# charlie_array_v1.net
KiCad netlist of a schematic drawn in EAGLE
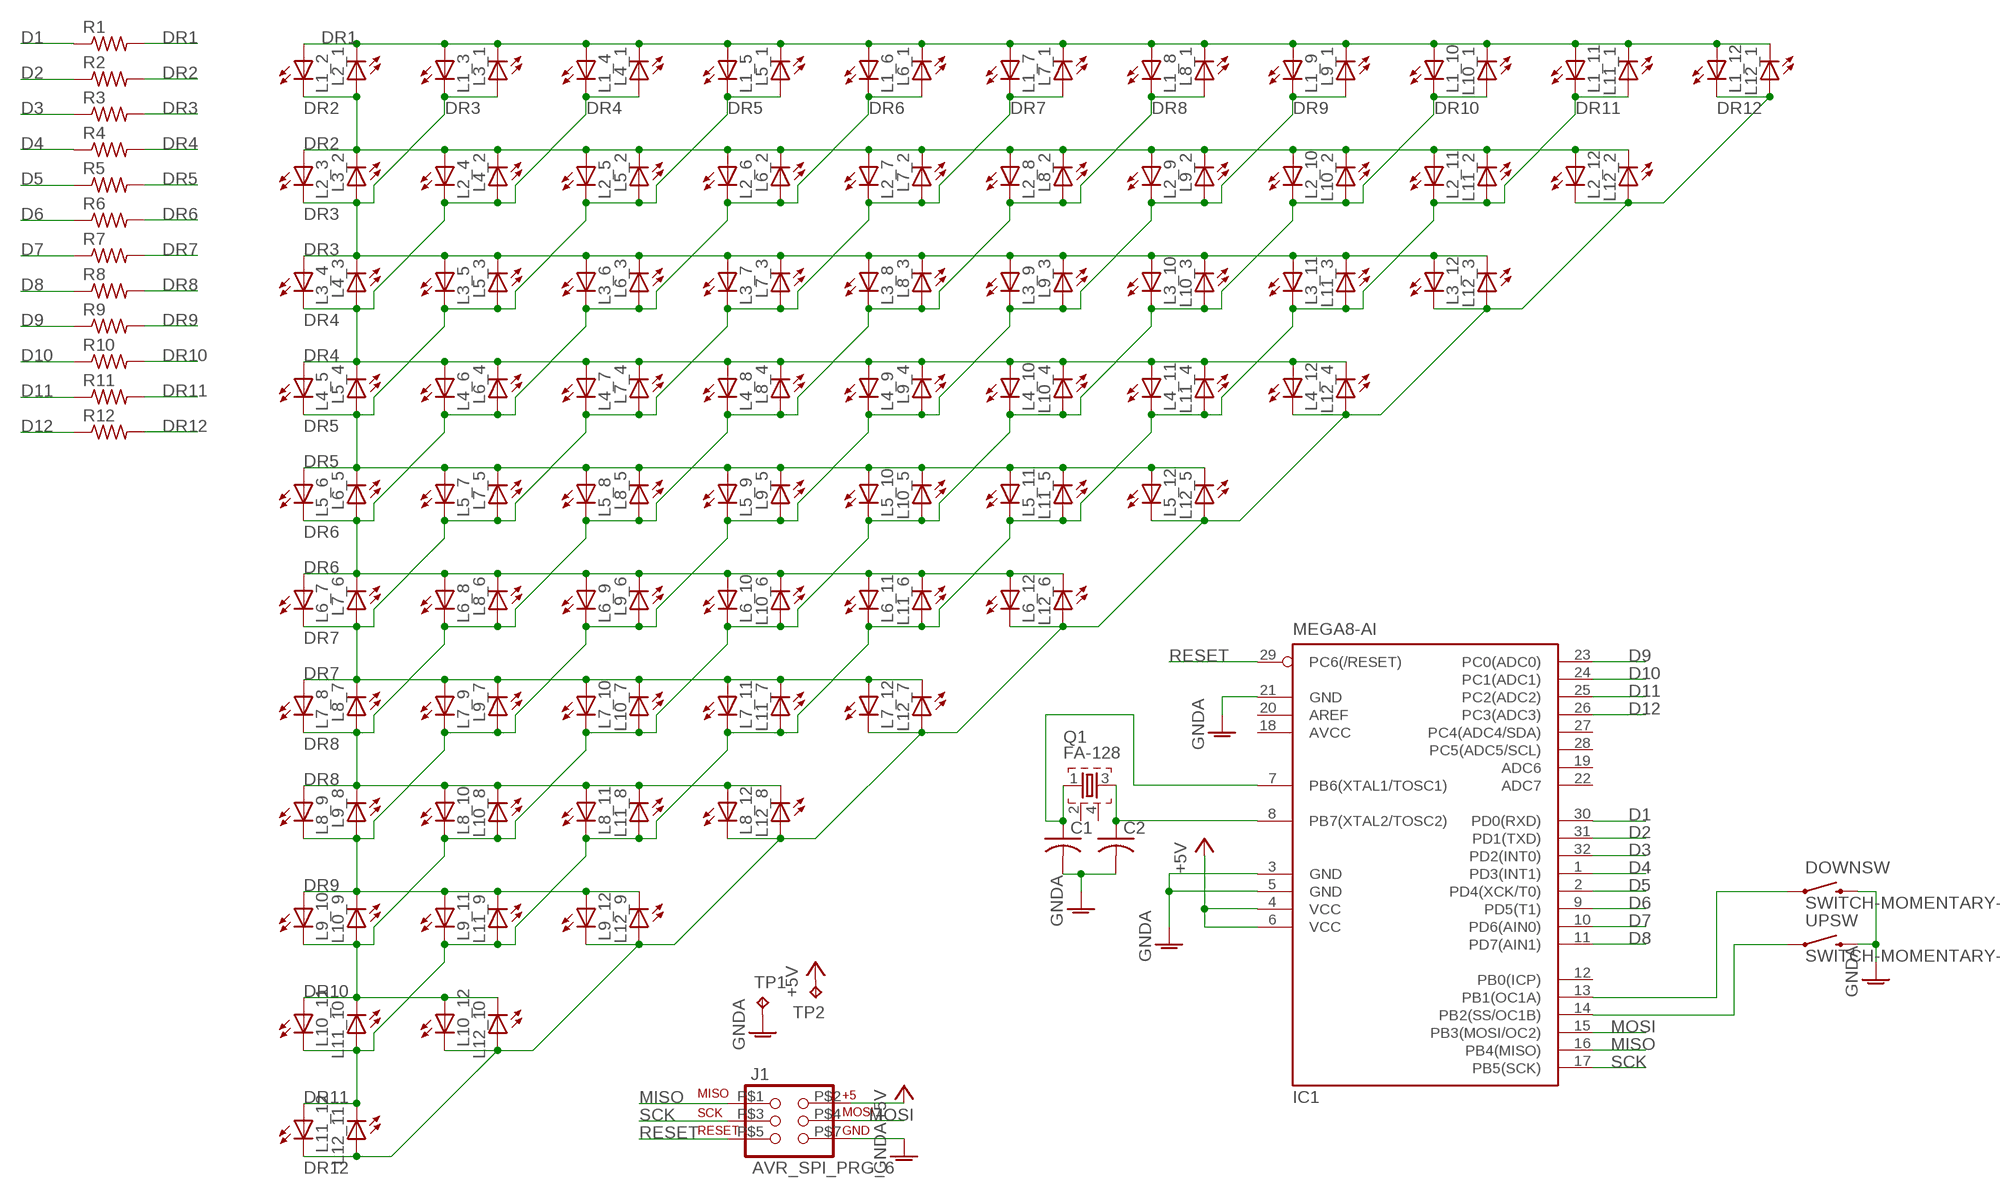
[diagram p0: schematic, sheet 1]

(export (version "E")
  (design (tool "Eeschema 10.0.6"))
  (components
    (comp (ref "C1")
      (value "C-USC0603")
      (footprint "eagle-import:C0603")
      (libsource (lib "eagle-import") (part "C-USC0603"))
    )
    (comp (ref "C2")
      (value "C-USC0603")
      (footprint "eagle-import:C0603")
      (libsource (lib "eagle-import") (part "C-USC0603"))
    )
    (comp (ref "DOWNSW")
      (value "SWITCH-MOMENTARY-2")
      (footprint "eagle-import:TACTILE_SWITCH_TALL")
      (libsource (lib "eagle-import") (part "SWITCH-MOMENTARY-2"))
    )
    (comp (ref "IC1")
      (value "MEGA8-AI")
      (footprint "eagle-import:TQFP32-08")
      (fields (field (name "MPN") "ATMEGA8-16AU"))
      (libsource (lib "eagle-import") (part "MEGA8-AI"))
    )
    (comp (ref "J1")
      (value "AVR_SPI_PRG_6")
      (footprint "eagle-import:2X3_ICSP_SMD")
      (libsource (lib "eagle-import") (part "AVR_SPI_PRG_6"))
    )
    (comp (ref "L1_2")
      (value "LEDCHIPLED_0603")
      (footprint "eagle-import:CHIPLED_0603")
      (libsource (lib "eagle-import") (part "LEDCHIPLED_0603"))
    )
    (comp (ref "L1_3")
      (value "LEDCHIPLED_0603")
      (footprint "eagle-import:CHIPLED_0603")
      (libsource (lib "eagle-import") (part "LEDCHIPLED_0603"))
    )
    (comp (ref "L1_4")
      (value "LEDCHIPLED_0603")
      (footprint "eagle-import:CHIPLED_0603")
      (libsource (lib "eagle-import") (part "LEDCHIPLED_0603"))
    )
    (comp (ref "L1_5")
      (value "LEDCHIPLED_0603")
      (footprint "eagle-import:CHIPLED_0603")
      (libsource (lib "eagle-import") (part "LEDCHIPLED_0603"))
    )
    (comp (ref "L1_6")
      (value "LEDCHIPLED_0603")
      (footprint "eagle-import:CHIPLED_0603")
      (libsource (lib "eagle-import") (part "LEDCHIPLED_0603"))
    )
    (comp (ref "L1_7")
      (value "LEDCHIPLED_0603")
      (footprint "eagle-import:CHIPLED_0603")
      (libsource (lib "eagle-import") (part "LEDCHIPLED_0603"))
    )
    (comp (ref "L1_8")
      (value "LEDCHIPLED_0603")
      (footprint "eagle-import:CHIPLED_0603")
      (libsource (lib "eagle-import") (part "LEDCHIPLED_0603"))
    )
    (comp (ref "L1_9")
      (value "LEDCHIPLED_0603")
      (footprint "eagle-import:CHIPLED_0603")
      (libsource (lib "eagle-import") (part "LEDCHIPLED_0603"))
    )
    (comp (ref "L1_10")
      (value "LEDCHIPLED_0603")
      (footprint "eagle-import:CHIPLED_0603")
      (libsource (lib "eagle-import") (part "LEDCHIPLED_0603"))
    )
    (comp (ref "L1_11")
      (value "LEDCHIPLED_0603")
      (footprint "eagle-import:CHIPLED_0603")
      (libsource (lib "eagle-import") (part "LEDCHIPLED_0603"))
    )
    (comp (ref "L1_12")
      (value "LEDCHIPLED_0603")
      (footprint "eagle-import:CHIPLED_0603")
      (libsource (lib "eagle-import") (part "LEDCHIPLED_0603"))
    )
    (comp (ref "L2_1")
      (value "LEDCHIPLED_0603")
      (footprint "eagle-import:CHIPLED_0603")
      (libsource (lib "eagle-import") (part "LEDCHIPLED_0603"))
    )
    (comp (ref "L2_3")
      (value "LEDCHIPLED_0603")
      (footprint "eagle-import:CHIPLED_0603")
      (libsource (lib "eagle-import") (part "LEDCHIPLED_0603"))
    )
    (comp (ref "L2_4")
      (value "LEDCHIPLED_0603")
      (footprint "eagle-import:CHIPLED_0603")
      (libsource (lib "eagle-import") (part "LEDCHIPLED_0603"))
    )
    (comp (ref "L2_5")
      (value "LEDCHIPLED_0603")
      (footprint "eagle-import:CHIPLED_0603")
      (libsource (lib "eagle-import") (part "LEDCHIPLED_0603"))
    )
    (comp (ref "L2_6")
      (value "LEDCHIPLED_0603")
      (footprint "eagle-import:CHIPLED_0603")
      (libsource (lib "eagle-import") (part "LEDCHIPLED_0603"))
    )
    (comp (ref "L2_7")
      (value "LEDCHIPLED_0603")
      (footprint "eagle-import:CHIPLED_0603")
      (libsource (lib "eagle-import") (part "LEDCHIPLED_0603"))
    )
    (comp (ref "L2_8")
      (value "LEDCHIPLED_0603")
      (footprint "eagle-import:CHIPLED_0603")
      (libsource (lib "eagle-import") (part "LEDCHIPLED_0603"))
    )
    (comp (ref "L2_9")
      (value "LEDCHIPLED_0603")
      (footprint "eagle-import:CHIPLED_0603")
      (libsource (lib "eagle-import") (part "LEDCHIPLED_0603"))
    )
    (comp (ref "L2_10")
      (value "LEDCHIPLED_0603")
      (footprint "eagle-import:CHIPLED_0603")
      (libsource (lib "eagle-import") (part "LEDCHIPLED_0603"))
    )
    (comp (ref "L2_11")
      (value "LEDCHIPLED_0603")
      (footprint "eagle-import:CHIPLED_0603")
      (libsource (lib "eagle-import") (part "LEDCHIPLED_0603"))
    )
    (comp (ref "L2_12")
      (value "LEDCHIPLED_0603")
      (footprint "eagle-import:CHIPLED_0603")
      (libsource (lib "eagle-import") (part "LEDCHIPLED_0603"))
    )
    (comp (ref "L3_1")
      (value "LEDCHIPLED_0603")
      (footprint "eagle-import:CHIPLED_0603")
      (libsource (lib "eagle-import") (part "LEDCHIPLED_0603"))
    )
    (comp (ref "L3_2")
      (value "LEDCHIPLED_0603")
      (footprint "eagle-import:CHIPLED_0603")
      (libsource (lib "eagle-import") (part "LEDCHIPLED_0603"))
    )
    (comp (ref "L3_4")
      (value "LEDCHIPLED_0603")
      (footprint "eagle-import:CHIPLED_0603")
      (libsource (lib "eagle-import") (part "LEDCHIPLED_0603"))
    )
    (comp (ref "L3_5")
      (value "LEDCHIPLED_0603")
      (footprint "eagle-import:CHIPLED_0603")
      (libsource (lib "eagle-import") (part "LEDCHIPLED_0603"))
    )
    (comp (ref "L3_6")
      (value "LEDCHIPLED_0603")
      (footprint "eagle-import:CHIPLED_0603")
      (libsource (lib "eagle-import") (part "LEDCHIPLED_0603"))
    )
    (comp (ref "L3_7")
      (value "LEDCHIPLED_0603")
      (footprint "eagle-import:CHIPLED_0603")
      (libsource (lib "eagle-import") (part "LEDCHIPLED_0603"))
    )
    (comp (ref "L3_8")
      (value "LEDCHIPLED_0603")
      (footprint "eagle-import:CHIPLED_0603")
      (libsource (lib "eagle-import") (part "LEDCHIPLED_0603"))
    )
    (comp (ref "L3_9")
      (value "LEDCHIPLED_0603")
      (footprint "eagle-import:CHIPLED_0603")
      (libsource (lib "eagle-import") (part "LEDCHIPLED_0603"))
    )
    (comp (ref "L3_10")
      (value "LEDCHIPLED_0603")
      (footprint "eagle-import:CHIPLED_0603")
      (libsource (lib "eagle-import") (part "LEDCHIPLED_0603"))
    )
    (comp (ref "L3_11")
      (value "LEDCHIPLED_0603")
      (footprint "eagle-import:CHIPLED_0603")
      (libsource (lib "eagle-import") (part "LEDCHIPLED_0603"))
    )
    (comp (ref "L3_12")
      (value "LEDCHIPLED_0603")
      (footprint "eagle-import:CHIPLED_0603")
      (libsource (lib "eagle-import") (part "LEDCHIPLED_0603"))
    )
    (comp (ref "L4_1")
      (value "LEDCHIPLED_0603")
      (footprint "eagle-import:CHIPLED_0603")
      (libsource (lib "eagle-import") (part "LEDCHIPLED_0603"))
    )
    (comp (ref "L4_2")
      (value "LEDCHIPLED_0603")
      (footprint "eagle-import:CHIPLED_0603")
      (libsource (lib "eagle-import") (part "LEDCHIPLED_0603"))
    )
    (comp (ref "L4_3")
      (value "LEDCHIPLED_0603")
      (footprint "eagle-import:CHIPLED_0603")
      (libsource (lib "eagle-import") (part "LEDCHIPLED_0603"))
    )
    (comp (ref "L4_5")
      (value "LEDCHIPLED_0603")
      (footprint "eagle-import:CHIPLED_0603")
      (libsource (lib "eagle-import") (part "LEDCHIPLED_0603"))
    )
    (comp (ref "L4_6")
      (value "LEDCHIPLED_0603")
      (footprint "eagle-import:CHIPLED_0603")
      (libsource (lib "eagle-import") (part "LEDCHIPLED_0603"))
    )
    (comp (ref "L4_7")
      (value "LEDCHIPLED_0603")
      (footprint "eagle-import:CHIPLED_0603")
      (libsource (lib "eagle-import") (part "LEDCHIPLED_0603"))
    )
    (comp (ref "L4_8")
      (value "LEDCHIPLED_0603")
      (footprint "eagle-import:CHIPLED_0603")
      (libsource (lib "eagle-import") (part "LEDCHIPLED_0603"))
    )
    (comp (ref "L4_9")
      (value "LEDCHIPLED_0603")
      (footprint "eagle-import:CHIPLED_0603")
      (libsource (lib "eagle-import") (part "LEDCHIPLED_0603"))
    )
    (comp (ref "L4_10")
      (value "LEDCHIPLED_0603")
      (footprint "eagle-import:CHIPLED_0603")
      (libsource (lib "eagle-import") (part "LEDCHIPLED_0603"))
    )
    (comp (ref "L4_11")
      (value "LEDCHIPLED_0603")
      (footprint "eagle-import:CHIPLED_0603")
      (libsource (lib "eagle-import") (part "LEDCHIPLED_0603"))
    )
    (comp (ref "L4_12")
      (value "LEDCHIPLED_0603")
      (footprint "eagle-import:CHIPLED_0603")
      (libsource (lib "eagle-import") (part "LEDCHIPLED_0603"))
    )
    (comp (ref "L5_1")
      (value "LEDCHIPLED_0603")
      (footprint "eagle-import:CHIPLED_0603")
      (libsource (lib "eagle-import") (part "LEDCHIPLED_0603"))
    )
    (comp (ref "L5_2")
      (value "LEDCHIPLED_0603")
      (footprint "eagle-import:CHIPLED_0603")
      (libsource (lib "eagle-import") (part "LEDCHIPLED_0603"))
    )
    (comp (ref "L5_3")
      (value "LEDCHIPLED_0603")
      (footprint "eagle-import:CHIPLED_0603")
      (libsource (lib "eagle-import") (part "LEDCHIPLED_0603"))
    )
    (comp (ref "L5_4")
      (value "LEDCHIPLED_0603")
      (footprint "eagle-import:CHIPLED_0603")
      (libsource (lib "eagle-import") (part "LEDCHIPLED_0603"))
    )
    (comp (ref "L5_6")
      (value "LEDCHIPLED_0603")
      (footprint "eagle-import:CHIPLED_0603")
      (libsource (lib "eagle-import") (part "LEDCHIPLED_0603"))
    )
    (comp (ref "L5_7")
      (value "LEDCHIPLED_0603")
      (footprint "eagle-import:CHIPLED_0603")
      (libsource (lib "eagle-import") (part "LEDCHIPLED_0603"))
    )
    (comp (ref "L5_8")
      (value "LEDCHIPLED_0603")
      (footprint "eagle-import:CHIPLED_0603")
      (libsource (lib "eagle-import") (part "LEDCHIPLED_0603"))
    )
    (comp (ref "L5_9")
      (value "LEDCHIPLED_0603")
      (footprint "eagle-import:CHIPLED_0603")
      (libsource (lib "eagle-import") (part "LEDCHIPLED_0603"))
    )
    (comp (ref "L5_10")
      (value "LEDCHIPLED_0603")
      (footprint "eagle-import:CHIPLED_0603")
      (libsource (lib "eagle-import") (part "LEDCHIPLED_0603"))
    )
    (comp (ref "L5_11")
      (value "LEDCHIPLED_0603")
      (footprint "eagle-import:CHIPLED_0603")
      (libsource (lib "eagle-import") (part "LEDCHIPLED_0603"))
    )
    (comp (ref "L5_12")
      (value "LEDCHIPLED_0603")
      (footprint "eagle-import:CHIPLED_0603")
      (libsource (lib "eagle-import") (part "LEDCHIPLED_0603"))
    )
    (comp (ref "L6_1")
      (value "LEDCHIPLED_0603")
      (footprint "eagle-import:CHIPLED_0603")
      (libsource (lib "eagle-import") (part "LEDCHIPLED_0603"))
    )
    (comp (ref "L6_2")
      (value "LEDCHIPLED_0603")
      (footprint "eagle-import:CHIPLED_0603")
      (libsource (lib "eagle-import") (part "LEDCHIPLED_0603"))
    )
    (comp (ref "L6_3")
      (value "LEDCHIPLED_0603")
      (footprint "eagle-import:CHIPLED_0603")
      (libsource (lib "eagle-import") (part "LEDCHIPLED_0603"))
    )
    (comp (ref "L6_4")
      (value "LEDCHIPLED_0603")
      (footprint "eagle-import:CHIPLED_0603")
      (libsource (lib "eagle-import") (part "LEDCHIPLED_0603"))
    )
    (comp (ref "L6_5")
      (value "LEDCHIPLED_0603")
      (footprint "eagle-import:CHIPLED_0603")
      (libsource (lib "eagle-import") (part "LEDCHIPLED_0603"))
    )
    (comp (ref "L6_7")
      (value "LEDCHIPLED_0603")
      (footprint "eagle-import:CHIPLED_0603")
      (libsource (lib "eagle-import") (part "LEDCHIPLED_0603"))
    )
    (comp (ref "L6_8")
      (value "LEDCHIPLED_0603")
      (footprint "eagle-import:CHIPLED_0603")
      (libsource (lib "eagle-import") (part "LEDCHIPLED_0603"))
    )
    (comp (ref "L6_9")
      (value "LEDCHIPLED_0603")
      (footprint "eagle-import:CHIPLED_0603")
      (libsource (lib "eagle-import") (part "LEDCHIPLED_0603"))
    )
    (comp (ref "L6_10")
      (value "LEDCHIPLED_0603")
      (footprint "eagle-import:CHIPLED_0603")
      (libsource (lib "eagle-import") (part "LEDCHIPLED_0603"))
    )
    (comp (ref "L6_11")
      (value "LEDCHIPLED_0603")
      (footprint "eagle-import:CHIPLED_0603")
      (libsource (lib "eagle-import") (part "LEDCHIPLED_0603"))
    )
    (comp (ref "L6_12")
      (value "LEDCHIPLED_0603")
      (footprint "eagle-import:CHIPLED_0603")
      (libsource (lib "eagle-import") (part "LEDCHIPLED_0603"))
    )
    (comp (ref "L7_1")
      (value "LEDCHIPLED_0603")
      (footprint "eagle-import:CHIPLED_0603")
      (libsource (lib "eagle-import") (part "LEDCHIPLED_0603"))
    )
    (comp (ref "L7_2")
      (value "LEDCHIPLED_0603")
      (footprint "eagle-import:CHIPLED_0603")
      (libsource (lib "eagle-import") (part "LEDCHIPLED_0603"))
    )
    (comp (ref "L7_3")
      (value "LEDCHIPLED_0603")
      (footprint "eagle-import:CHIPLED_0603")
      (libsource (lib "eagle-import") (part "LEDCHIPLED_0603"))
    )
    (comp (ref "L7_4")
      (value "LEDCHIPLED_0603")
      (footprint "eagle-import:CHIPLED_0603")
      (libsource (lib "eagle-import") (part "LEDCHIPLED_0603"))
    )
    (comp (ref "L7_5")
      (value "LEDCHIPLED_0603")
      (footprint "eagle-import:CHIPLED_0603")
      (libsource (lib "eagle-import") (part "LEDCHIPLED_0603"))
    )
    (comp (ref "L7_6")
      (value "LEDCHIPLED_0603")
      (footprint "eagle-import:CHIPLED_0603")
      (libsource (lib "eagle-import") (part "LEDCHIPLED_0603"))
    )
    (comp (ref "L7_8")
      (value "LEDCHIPLED_0603")
      (footprint "eagle-import:CHIPLED_0603")
      (libsource (lib "eagle-import") (part "LEDCHIPLED_0603"))
    )
    (comp (ref "L7_9")
      (value "LEDCHIPLED_0603")
      (footprint "eagle-import:CHIPLED_0603")
      (libsource (lib "eagle-import") (part "LEDCHIPLED_0603"))
    )
    (comp (ref "L7_10")
      (value "LEDCHIPLED_0603")
      (footprint "eagle-import:CHIPLED_0603")
      (libsource (lib "eagle-import") (part "LEDCHIPLED_0603"))
    )
    (comp (ref "L7_11")
      (value "LEDCHIPLED_0603")
      (footprint "eagle-import:CHIPLED_0603")
      (libsource (lib "eagle-import") (part "LEDCHIPLED_0603"))
    )
    (comp (ref "L7_12")
      (value "LEDCHIPLED_0603")
      (footprint "eagle-import:CHIPLED_0603")
      (libsource (lib "eagle-import") (part "LEDCHIPLED_0603"))
    )
    (comp (ref "L8_1")
      (value "LEDCHIPLED_0603")
      (footprint "eagle-import:CHIPLED_0603")
      (libsource (lib "eagle-import") (part "LEDCHIPLED_0603"))
    )
    (comp (ref "L8_2")
      (value "LEDCHIPLED_0603")
      (footprint "eagle-import:CHIPLED_0603")
      (libsource (lib "eagle-import") (part "LEDCHIPLED_0603"))
    )
    (comp (ref "L8_3")
      (value "LEDCHIPLED_0603")
      (footprint "eagle-import:CHIPLED_0603")
      (libsource (lib "eagle-import") (part "LEDCHIPLED_0603"))
    )
    (comp (ref "L8_4")
      (value "LEDCHIPLED_0603")
      (footprint "eagle-import:CHIPLED_0603")
      (libsource (lib "eagle-import") (part "LEDCHIPLED_0603"))
    )
    (comp (ref "L8_5")
      (value "LEDCHIPLED_0603")
      (footprint "eagle-import:CHIPLED_0603")
      (libsource (lib "eagle-import") (part "LEDCHIPLED_0603"))
    )
    (comp (ref "L8_6")
      (value "LEDCHIPLED_0603")
      (footprint "eagle-import:CHIPLED_0603")
      (libsource (lib "eagle-import") (part "LEDCHIPLED_0603"))
    )
    (comp (ref "L8_7")
      (value "LEDCHIPLED_0603")
      (footprint "eagle-import:CHIPLED_0603")
      (libsource (lib "eagle-import") (part "LEDCHIPLED_0603"))
    )
    (comp (ref "L8_9")
      (value "LEDCHIPLED_0603")
      (footprint "eagle-import:CHIPLED_0603")
      (libsource (lib "eagle-import") (part "LEDCHIPLED_0603"))
    )
    (comp (ref "L8_10")
      (value "LEDCHIPLED_0603")
      (footprint "eagle-import:CHIPLED_0603")
      (libsource (lib "eagle-import") (part "LEDCHIPLED_0603"))
    )
    (comp (ref "L8_11")
      (value "LEDCHIPLED_0603")
      (footprint "eagle-import:CHIPLED_0603")
      (libsource (lib "eagle-import") (part "LEDCHIPLED_0603"))
    )
    (comp (ref "L8_12")
      (value "LEDCHIPLED_0603")
      (footprint "eagle-import:CHIPLED_0603")
      (libsource (lib "eagle-import") (part "LEDCHIPLED_0603"))
    )
    (comp (ref "L9_1")
      (value "LEDCHIPLED_0603")
      (footprint "eagle-import:CHIPLED_0603")
      (libsource (lib "eagle-import") (part "LEDCHIPLED_0603"))
    )
    (comp (ref "L9_2")
      (value "LEDCHIPLED_0603")
      (footprint "eagle-import:CHIPLED_0603")
      (libsource (lib "eagle-import") (part "LEDCHIPLED_0603"))
    )
    (comp (ref "L9_3")
      (value "LEDCHIPLED_0603")
      (footprint "eagle-import:CHIPLED_0603")
      (libsource (lib "eagle-import") (part "LEDCHIPLED_0603"))
    )
    (comp (ref "L9_4")
      (value "LEDCHIPLED_0603")
      (footprint "eagle-import:CHIPLED_0603")
      (libsource (lib "eagle-import") (part "LEDCHIPLED_0603"))
    )
    (comp (ref "L9_5")
      (value "LEDCHIPLED_0603")
      (footprint "eagle-import:CHIPLED_0603")
      (libsource (lib "eagle-import") (part "LEDCHIPLED_0603"))
    )
    (comp (ref "L9_6")
      (value "LEDCHIPLED_0603")
      (footprint "eagle-import:CHIPLED_0603")
      (libsource (lib "eagle-import") (part "LEDCHIPLED_0603"))
    )
    (comp (ref "L9_7")
      (value "LEDCHIPLED_0603")
      (footprint "eagle-import:CHIPLED_0603")
      (libsource (lib "eagle-import") (part "LEDCHIPLED_0603"))
    )
    (comp (ref "L9_8")
      (value "LEDCHIPLED_0603")
      (footprint "eagle-import:CHIPLED_0603")
      (libsource (lib "eagle-import") (part "LEDCHIPLED_0603"))
    )
    (comp (ref "L9_10")
      (value "LEDCHIPLED_0603")
      (footprint "eagle-import:CHIPLED_0603")
      (libsource (lib "eagle-import") (part "LEDCHIPLED_0603"))
    )
    (comp (ref "L9_11")
      (value "LEDCHIPLED_0603")
      (footprint "eagle-import:CHIPLED_0603")
      (libsource (lib "eagle-import") (part "LEDCHIPLED_0603"))
    )
    (comp (ref "L9_12")
      (value "LEDCHIPLED_0603")
      (footprint "eagle-import:CHIPLED_0603")
      (libsource (lib "eagle-import") (part "LEDCHIPLED_0603"))
    )
    (comp (ref "L10_1")
      (value "LEDCHIPLED_0603")
      (footprint "eagle-import:CHIPLED_0603")
      (libsource (lib "eagle-import") (part "LEDCHIPLED_0603"))
    )
    (comp (ref "L10_2")
      (value "LEDCHIPLED_0603")
      (footprint "eagle-import:CHIPLED_0603")
      (libsource (lib "eagle-import") (part "LEDCHIPLED_0603"))
    )
    (comp (ref "L10_3")
      (value "LEDCHIPLED_0603")
      (footprint "eagle-import:CHIPLED_0603")
      (libsource (lib "eagle-import") (part "LEDCHIPLED_0603"))
    )
    (comp (ref "L10_4")
      (value "LEDCHIPLED_0603")
      (footprint "eagle-import:CHIPLED_0603")
      (libsource (lib "eagle-import") (part "LEDCHIPLED_0603"))
    )
    (comp (ref "L10_5")
      (value "LEDCHIPLED_0603")
      (footprint "eagle-import:CHIPLED_0603")
      (libsource (lib "eagle-import") (part "LEDCHIPLED_0603"))
    )
    (comp (ref "L10_6")
      (value "LEDCHIPLED_0603")
      (footprint "eagle-import:CHIPLED_0603")
      (libsource (lib "eagle-import") (part "LEDCHIPLED_0603"))
    )
    (comp (ref "L10_7")
      (value "LEDCHIPLED_0603")
      (footprint "eagle-import:CHIPLED_0603")
      (libsource (lib "eagle-import") (part "LEDCHIPLED_0603"))
    )
    (comp (ref "L10_8")
      (value "LEDCHIPLED_0603")
      (footprint "eagle-import:CHIPLED_0603")
      (libsource (lib "eagle-import") (part "LEDCHIPLED_0603"))
    )
    (comp (ref "L10_9")
      (value "LEDCHIPLED_0603")
      (footprint "eagle-import:CHIPLED_0603")
      (libsource (lib "eagle-import") (part "LEDCHIPLED_0603"))
    )
    (comp (ref "L10_11")
      (value "LEDCHIPLED_0603")
      (footprint "eagle-import:CHIPLED_0603")
      (libsource (lib "eagle-import") (part "LEDCHIPLED_0603"))
    )
    (comp (ref "L10_12")
      (value "LEDCHIPLED_0603")
      (footprint "eagle-import:CHIPLED_0603")
      (libsource (lib "eagle-import") (part "LEDCHIPLED_0603"))
    )
    (comp (ref "L11_1")
      (value "LEDCHIPLED_0603")
      (footprint "eagle-import:CHIPLED_0603")
      (libsource (lib "eagle-import") (part "LEDCHIPLED_0603"))
    )
    (comp (ref "L11_2")
      (value "LEDCHIPLED_0603")
      (footprint "eagle-import:CHIPLED_0603")
      (libsource (lib "eagle-import") (part "LEDCHIPLED_0603"))
    )
    (comp (ref "L11_3")
      (value "LEDCHIPLED_0603")
      (footprint "eagle-import:CHIPLED_0603")
      (libsource (lib "eagle-import") (part "LEDCHIPLED_0603"))
    )
    (comp (ref "L11_4")
      (value "LEDCHIPLED_0603")
      (footprint "eagle-import:CHIPLED_0603")
      (libsource (lib "eagle-import") (part "LEDCHIPLED_0603"))
    )
    (comp (ref "L11_5")
      (value "LEDCHIPLED_0603")
      (footprint "eagle-import:CHIPLED_0603")
      (libsource (lib "eagle-import") (part "LEDCHIPLED_0603"))
    )
    (comp (ref "L11_6")
      (value "LEDCHIPLED_0603")
      (footprint "eagle-import:CHIPLED_0603")
      (libsource (lib "eagle-import") (part "LEDCHIPLED_0603"))
    )
    (comp (ref "L11_7")
      (value "LEDCHIPLED_0603")
      (footprint "eagle-import:CHIPLED_0603")
      (libsource (lib "eagle-import") (part "LEDCHIPLED_0603"))
    )
    (comp (ref "L11_8")
      (value "LEDCHIPLED_0603")
      (footprint "eagle-import:CHIPLED_0603")
      (libsource (lib "eagle-import") (part "LEDCHIPLED_0603"))
    )
    (comp (ref "L11_9")
      (value "LEDCHIPLED_0603")
      (footprint "eagle-import:CHIPLED_0603")
      (libsource (lib "eagle-import") (part "LEDCHIPLED_0603"))
    )
    (comp (ref "L11_10")
      (value "LEDCHIPLED_0603")
      (footprint "eagle-import:CHIPLED_0603")
      (libsource (lib "eagle-import") (part "LEDCHIPLED_0603"))
    )
    (comp (ref "L11_12")
      (value "LEDCHIPLED_0603")
      (footprint "eagle-import:CHIPLED_0603")
      (libsource (lib "eagle-import") (part "LEDCHIPLED_0603"))
    )
    (comp (ref "L12_1")
      (value "LEDCHIPLED_0603")
      (footprint "eagle-import:CHIPLED_0603")
      (libsource (lib "eagle-import") (part "LEDCHIPLED_0603"))
    )
    (comp (ref "L12_2")
      (value "LEDCHIPLED_0603")
      (footprint "eagle-import:CHIPLED_0603")
      (libsource (lib "eagle-import") (part "LEDCHIPLED_0603"))
    )
    (comp (ref "L12_3")
      (value "LEDCHIPLED_0603")
      (footprint "eagle-import:CHIPLED_0603")
      (libsource (lib "eagle-import") (part "LEDCHIPLED_0603"))
    )
    (comp (ref "L12_4")
      (value "LEDCHIPLED_0603")
      (footprint "eagle-import:CHIPLED_0603")
      (libsource (lib "eagle-import") (part "LEDCHIPLED_0603"))
    )
    (comp (ref "L12_5")
      (value "LEDCHIPLED_0603")
      (footprint "eagle-import:CHIPLED_0603")
      (libsource (lib "eagle-import") (part "LEDCHIPLED_0603"))
    )
    (comp (ref "L12_6")
      (value "LEDCHIPLED_0603")
      (footprint "eagle-import:CHIPLED_0603")
      (libsource (lib "eagle-import") (part "LEDCHIPLED_0603"))
    )
    (comp (ref "L12_7")
      (value "LEDCHIPLED_0603")
      (footprint "eagle-import:CHIPLED_0603")
      (libsource (lib "eagle-import") (part "LEDCHIPLED_0603"))
    )
    (comp (ref "L12_8")
      (value "LEDCHIPLED_0603")
      (footprint "eagle-import:CHIPLED_0603")
      (libsource (lib "eagle-import") (part "LEDCHIPLED_0603"))
    )
    (comp (ref "L12_9")
      (value "LEDCHIPLED_0603")
      (footprint "eagle-import:CHIPLED_0603")
      (libsource (lib "eagle-import") (part "LEDCHIPLED_0603"))
    )
    (comp (ref "L12_10")
      (value "LEDCHIPLED_0603")
      (footprint "eagle-import:CHIPLED_0603")
      (libsource (lib "eagle-import") (part "LEDCHIPLED_0603"))
    )
    (comp (ref "L12_11")
      (value "LEDCHIPLED_0603")
      (footprint "eagle-import:CHIPLED_0603")
      (libsource (lib "eagle-import") (part "LEDCHIPLED_0603"))
    )
    (comp (ref "Q1")
      (value "FA-128")
      (footprint "eagle-import:FA-128")
      (libsource (lib "eagle-import") (part "FA-128"))
    )
    (comp (ref "R1")
      (value "R-US_R0603")
      (footprint "eagle-import:R0603")
      (libsource (lib "eagle-import") (part "R-US_R0603"))
    )
    (comp (ref "R2")
      (value "R-US_R0603")
      (footprint "eagle-import:R0603")
      (libsource (lib "eagle-import") (part "R-US_R0603"))
    )
    (comp (ref "R3")
      (value "R-US_R0603")
      (footprint "eagle-import:R0603")
      (libsource (lib "eagle-import") (part "R-US_R0603"))
    )
    (comp (ref "R4")
      (value "R-US_R0603")
      (footprint "eagle-import:R0603")
      (libsource (lib "eagle-import") (part "R-US_R0603"))
    )
    (comp (ref "R5")
      (value "R-US_R0603")
      (footprint "eagle-import:R0603")
      (libsource (lib "eagle-import") (part "R-US_R0603"))
    )
    (comp (ref "R6")
      (value "R-US_R0603")
      (footprint "eagle-import:R0603")
      (libsource (lib "eagle-import") (part "R-US_R0603"))
    )
    (comp (ref "R7")
      (value "R-US_R0603")
      (footprint "eagle-import:R0603")
      (libsource (lib "eagle-import") (part "R-US_R0603"))
    )
    (comp (ref "R8")
      (value "R-US_R0603")
      (footprint "eagle-import:R0603")
      (libsource (lib "eagle-import") (part "R-US_R0603"))
    )
    (comp (ref "R9")
      (value "R-US_R0603")
      (footprint "eagle-import:R0603")
      (libsource (lib "eagle-import") (part "R-US_R0603"))
    )
    (comp (ref "R10")
      (value "R-US_R0603")
      (footprint "eagle-import:R0603")
      (libsource (lib "eagle-import") (part "R-US_R0603"))
    )
    (comp (ref "R11")
      (value "R-US_R0603")
      (footprint "eagle-import:R0603")
      (libsource (lib "eagle-import") (part "R-US_R0603"))
    )
    (comp (ref "R12")
      (value "R-US_R0603")
      (footprint "eagle-import:R0603")
      (libsource (lib "eagle-import") (part "R-US_R0603"))
    )
    (comp (ref "TP1")
      (value "TPTP20SQ")
      (footprint "eagle-import:TP20SQ")
      (libsource (lib "eagle-import") (part "TPTP20SQ"))
    )
    (comp (ref "TP2")
      (value "TPTP20SQ")
      (footprint "eagle-import:TP20SQ")
      (libsource (lib "eagle-import") (part "TPTP20SQ"))
    )
    (comp (ref "UPSW")
      (value "SWITCH-MOMENTARY-2")
      (footprint "eagle-import:TACTILE_SWITCH_TALL")
      (libsource (lib "eagle-import") (part "SWITCH-MOMENTARY-2"))
    )
  )
  (nets
    (net (code "1") (name "+5V") (class "Default")
      (node (ref "IC1") (pin "4") (pinfunction "VCC_4") (pintype "power_in"))
      (node (ref "IC1") (pin "6") (pinfunction "VCC_6") (pintype "power_in"))
      (node (ref "J1") (pin "P$2") (pinfunction "2_P$2") (pintype "passive"))
      (node (ref "TP2") (pin "TP") (pinfunction "TP_TP") (pintype "input"))
    )
    (net (code "2") (name "/AVCC") (class "Default")
      (node (ref "IC1") (pin "18") (pinfunction "AVCC_18") (pintype "power_in"))
    )
    (net (code "3") (name "/D1") (class "Default")
      (node (ref "IC1") (pin "30") (pinfunction "PD0(RXD)_30") (pintype "bidirectional"))
      (node (ref "R1") (pin "1") (pinfunction "1_1") (pintype "passive"))
    )
    (net (code "4") (name "/D2") (class "Default")
      (node (ref "IC1") (pin "31") (pinfunction "PD1(TXD)_31") (pintype "bidirectional"))
      (node (ref "R2") (pin "1") (pinfunction "1_1") (pintype "passive"))
    )
    (net (code "5") (name "/D3") (class "Default")
      (node (ref "IC1") (pin "32") (pinfunction "PD2(INT0)_32") (pintype "bidirectional"))
      (node (ref "R3") (pin "1") (pinfunction "1_1") (pintype "passive"))
    )
    (net (code "6") (name "/D4") (class "Default")
      (node (ref "IC1") (pin "1") (pinfunction "PD3(INT1)_1") (pintype "bidirectional"))
      (node (ref "R4") (pin "1") (pinfunction "1_1") (pintype "passive"))
    )
    (net (code "7") (name "/D5") (class "Default")
      (node (ref "IC1") (pin "2") (pinfunction "PD4(XCK/T0)_2") (pintype "bidirectional"))
      (node (ref "R5") (pin "1") (pinfunction "1_1") (pintype "passive"))
    )
    (net (code "8") (name "/D6") (class "Default")
      (node (ref "IC1") (pin "9") (pinfunction "PD5(T1)_9") (pintype "bidirectional"))
      (node (ref "R6") (pin "1") (pinfunction "1_1") (pintype "passive"))
    )
    (net (code "9") (name "/D7") (class "Default")
      (node (ref "IC1") (pin "10") (pinfunction "PD6(AIN0)_10") (pintype "bidirectional"))
      (node (ref "R7") (pin "1") (pinfunction "1_1") (pintype "passive"))
    )
    (net (code "10") (name "/D8") (class "Default")
      (node (ref "IC1") (pin "11") (pinfunction "PD7(AIN1)_11") (pintype "bidirectional"))
      (node (ref "R8") (pin "1") (pinfunction "1_1") (pintype "passive"))
    )
    (net (code "11") (name "/D9") (class "Default")
      (node (ref "IC1") (pin "23") (pinfunction "PC0(ADC0)_23") (pintype "bidirectional"))
      (node (ref "R9") (pin "1") (pinfunction "1_1") (pintype "passive"))
    )
    (net (code "12") (name "/D10") (class "Default")
      (node (ref "IC1") (pin "24") (pinfunction "PC1(ADC1)_24") (pintype "bidirectional"))
      (node (ref "R10") (pin "1") (pinfunction "1_1") (pintype "passive"))
    )
    (net (code "13") (name "/D11") (class "Default")
      (node (ref "IC1") (pin "25") (pinfunction "PC2(ADC2)_25") (pintype "bidirectional"))
      (node (ref "R11") (pin "1") (pinfunction "1_1") (pintype "passive"))
    )
    (net (code "14") (name "/D12") (class "Default")
      (node (ref "IC1") (pin "26") (pinfunction "PC3(ADC3)_26") (pintype "bidirectional"))
      (node (ref "R12") (pin "1") (pinfunction "1_1") (pintype "passive"))
    )
    (net (code "15") (name "/DR1") (class "Default")
      (node (ref "L10_1") (pin "C") (pinfunction "C_C") (pintype "passive"))
      (node (ref "L11_1") (pin "C") (pinfunction "C_C") (pintype "passive"))
      (node (ref "L12_1") (pin "C") (pinfunction "C_C") (pintype "passive"))
      (node (ref "L1_10") (pin "A") (pinfunction "A_A") (pintype "passive"))
      (node (ref "L1_11") (pin "A") (pinfunction "A_A") (pintype "passive"))
      (node (ref "L1_12") (pin "A") (pinfunction "A_A") (pintype "passive"))
      (node (ref "L1_2") (pin "A") (pinfunction "A_A") (pintype "passive"))
      (node (ref "L1_3") (pin "A") (pinfunction "A_A") (pintype "passive"))
      (node (ref "L1_4") (pin "A") (pinfunction "A_A") (pintype "passive"))
      (node (ref "L1_5") (pin "A") (pinfunction "A_A") (pintype "passive"))
      (node (ref "L1_6") (pin "A") (pinfunction "A_A") (pintype "passive"))
      (node (ref "L1_7") (pin "A") (pinfunction "A_A") (pintype "passive"))
      (node (ref "L1_8") (pin "A") (pinfunction "A_A") (pintype "passive"))
      (node (ref "L1_9") (pin "A") (pinfunction "A_A") (pintype "passive"))
      (node (ref "L2_1") (pin "C") (pinfunction "C_C") (pintype "passive"))
      (node (ref "L3_1") (pin "C") (pinfunction "C_C") (pintype "passive"))
      (node (ref "L4_1") (pin "C") (pinfunction "C_C") (pintype "passive"))
      (node (ref "L5_1") (pin "C") (pinfunction "C_C") (pintype "passive"))
      (node (ref "L6_1") (pin "C") (pinfunction "C_C") (pintype "passive"))
      (node (ref "L7_1") (pin "C") (pinfunction "C_C") (pintype "passive"))
      (node (ref "L8_1") (pin "C") (pinfunction "C_C") (pintype "passive"))
      (node (ref "L9_1") (pin "C") (pinfunction "C_C") (pintype "passive"))
      (node (ref "R1") (pin "2") (pinfunction "2_2") (pintype "passive"))
    )
    (net (code "16") (name "/DR2") (class "Default")
      (node (ref "L10_2") (pin "C") (pinfunction "C_C") (pintype "passive"))
      (node (ref "L11_2") (pin "C") (pinfunction "C_C") (pintype "passive"))
      (node (ref "L12_2") (pin "C") (pinfunction "C_C") (pintype "passive"))
      (node (ref "L1_2") (pin "C") (pinfunction "C_C") (pintype "passive"))
      (node (ref "L2_1") (pin "A") (pinfunction "A_A") (pintype "passive"))
      (node (ref "L2_10") (pin "A") (pinfunction "A_A") (pintype "passive"))
      (node (ref "L2_11") (pin "A") (pinfunction "A_A") (pintype "passive"))
      (node (ref "L2_12") (pin "A") (pinfunction "A_A") (pintype "passive"))
      (node (ref "L2_3") (pin "A") (pinfunction "A_A") (pintype "passive"))
      (node (ref "L2_4") (pin "A") (pinfunction "A_A") (pintype "passive"))
      (node (ref "L2_5") (pin "A") (pinfunction "A_A") (pintype "passive"))
      (node (ref "L2_6") (pin "A") (pinfunction "A_A") (pintype "passive"))
      (node (ref "L2_7") (pin "A") (pinfunction "A_A") (pintype "passive"))
      (node (ref "L2_8") (pin "A") (pinfunction "A_A") (pintype "passive"))
      (node (ref "L2_9") (pin "A") (pinfunction "A_A") (pintype "passive"))
      (node (ref "L3_2") (pin "C") (pinfunction "C_C") (pintype "passive"))
      (node (ref "L4_2") (pin "C") (pinfunction "C_C") (pintype "passive"))
      (node (ref "L5_2") (pin "C") (pinfunction "C_C") (pintype "passive"))
      (node (ref "L6_2") (pin "C") (pinfunction "C_C") (pintype "passive"))
      (node (ref "L7_2") (pin "C") (pinfunction "C_C") (pintype "passive"))
      (node (ref "L8_2") (pin "C") (pinfunction "C_C") (pintype "passive"))
      (node (ref "L9_2") (pin "C") (pinfunction "C_C") (pintype "passive"))
      (node (ref "R2") (pin "2") (pinfunction "2_2") (pintype "passive"))
    )
    (net (code "17") (name "/DR3") (class "Default")
      (node (ref "L10_3") (pin "C") (pinfunction "C_C") (pintype "passive"))
      (node (ref "L11_3") (pin "C") (pinfunction "C_C") (pintype "passive"))
      (node (ref "L12_3") (pin "C") (pinfunction "C_C") (pintype "passive"))
      (node (ref "L1_3") (pin "C") (pinfunction "C_C") (pintype "passive"))
      (node (ref "L2_3") (pin "C") (pinfunction "C_C") (pintype "passive"))
      (node (ref "L3_1") (pin "A") (pinfunction "A_A") (pintype "passive"))
      (node (ref "L3_10") (pin "A") (pinfunction "A_A") (pintype "passive"))
      (node (ref "L3_11") (pin "A") (pinfunction "A_A") (pintype "passive"))
      (node (ref "L3_12") (pin "A") (pinfunction "A_A") (pintype "passive"))
      (node (ref "L3_2") (pin "A") (pinfunction "A_A") (pintype "passive"))
      (node (ref "L3_4") (pin "A") (pinfunction "A_A") (pintype "passive"))
      (node (ref "L3_5") (pin "A") (pinfunction "A_A") (pintype "passive"))
      (node (ref "L3_6") (pin "A") (pinfunction "A_A") (pintype "passive"))
      (node (ref "L3_7") (pin "A") (pinfunction "A_A") (pintype "passive"))
      (node (ref "L3_8") (pin "A") (pinfunction "A_A") (pintype "passive"))
      (node (ref "L3_9") (pin "A") (pinfunction "A_A") (pintype "passive"))
      (node (ref "L4_3") (pin "C") (pinfunction "C_C") (pintype "passive"))
      (node (ref "L5_3") (pin "C") (pinfunction "C_C") (pintype "passive"))
      (node (ref "L6_3") (pin "C") (pinfunction "C_C") (pintype "passive"))
      (node (ref "L7_3") (pin "C") (pinfunction "C_C") (pintype "passive"))
      (node (ref "L8_3") (pin "C") (pinfunction "C_C") (pintype "passive"))
      (node (ref "L9_3") (pin "C") (pinfunction "C_C") (pintype "passive"))
      (node (ref "R3") (pin "2") (pinfunction "2_2") (pintype "passive"))
    )
    (net (code "18") (name "/DR4") (class "Default")
      (node (ref "L10_4") (pin "C") (pinfunction "C_C") (pintype "passive"))
      (node (ref "L11_4") (pin "C") (pinfunction "C_C") (pintype "passive"))
      (node (ref "L12_4") (pin "C") (pinfunction "C_C") (pintype "passive"))
      (node (ref "L1_4") (pin "C") (pinfunction "C_C") (pintype "passive"))
      (node (ref "L2_4") (pin "C") (pinfunction "C_C") (pintype "passive"))
      (node (ref "L3_4") (pin "C") (pinfunction "C_C") (pintype "passive"))
      (node (ref "L4_1") (pin "A") (pinfunction "A_A") (pintype "passive"))
      (node (ref "L4_10") (pin "A") (pinfunction "A_A") (pintype "passive"))
      (node (ref "L4_11") (pin "A") (pinfunction "A_A") (pintype "passive"))
      (node (ref "L4_12") (pin "A") (pinfunction "A_A") (pintype "passive"))
      (node (ref "L4_2") (pin "A") (pinfunction "A_A") (pintype "passive"))
      (node (ref "L4_3") (pin "A") (pinfunction "A_A") (pintype "passive"))
      (node (ref "L4_5") (pin "A") (pinfunction "A_A") (pintype "passive"))
      (node (ref "L4_6") (pin "A") (pinfunction "A_A") (pintype "passive"))
      (node (ref "L4_7") (pin "A") (pinfunction "A_A") (pintype "passive"))
      (node (ref "L4_8") (pin "A") (pinfunction "A_A") (pintype "passive"))
      (node (ref "L4_9") (pin "A") (pinfunction "A_A") (pintype "passive"))
      (node (ref "L5_4") (pin "C") (pinfunction "C_C") (pintype "passive"))
      (node (ref "L6_4") (pin "C") (pinfunction "C_C") (pintype "passive"))
      (node (ref "L7_4") (pin "C") (pinfunction "C_C") (pintype "passive"))
      (node (ref "L8_4") (pin "C") (pinfunction "C_C") (pintype "passive"))
      (node (ref "L9_4") (pin "C") (pinfunction "C_C") (pintype "passive"))
      (node (ref "R4") (pin "2") (pinfunction "2_2") (pintype "passive"))
    )
    (net (code "19") (name "/DR5") (class "Default")
      (node (ref "L10_5") (pin "C") (pinfunction "C_C") (pintype "passive"))
      (node (ref "L11_5") (pin "C") (pinfunction "C_C") (pintype "passive"))
      (node (ref "L12_5") (pin "C") (pinfunction "C_C") (pintype "passive"))
      (node (ref "L1_5") (pin "C") (pinfunction "C_C") (pintype "passive"))
      (node (ref "L2_5") (pin "C") (pinfunction "C_C") (pintype "passive"))
      (node (ref "L3_5") (pin "C") (pinfunction "C_C") (pintype "passive"))
      (node (ref "L4_5") (pin "C") (pinfunction "C_C") (pintype "passive"))
      (node (ref "L5_1") (pin "A") (pinfunction "A_A") (pintype "passive"))
      (node (ref "L5_10") (pin "A") (pinfunction "A_A") (pintype "passive"))
      (node (ref "L5_11") (pin "A") (pinfunction "A_A") (pintype "passive"))
      (node (ref "L5_12") (pin "A") (pinfunction "A_A") (pintype "passive"))
      (node (ref "L5_2") (pin "A") (pinfunction "A_A") (pintype "passive"))
      (node (ref "L5_3") (pin "A") (pinfunction "A_A") (pintype "passive"))
      (node (ref "L5_4") (pin "A") (pinfunction "A_A") (pintype "passive"))
      (node (ref "L5_6") (pin "A") (pinfunction "A_A") (pintype "passive"))
      (node (ref "L5_7") (pin "A") (pinfunction "A_A") (pintype "passive"))
      (node (ref "L5_8") (pin "A") (pinfunction "A_A") (pintype "passive"))
      (node (ref "L5_9") (pin "A") (pinfunction "A_A") (pintype "passive"))
      (node (ref "L6_5") (pin "C") (pinfunction "C_C") (pintype "passive"))
      (node (ref "L7_5") (pin "C") (pinfunction "C_C") (pintype "passive"))
      (node (ref "L8_5") (pin "C") (pinfunction "C_C") (pintype "passive"))
      (node (ref "L9_5") (pin "C") (pinfunction "C_C") (pintype "passive"))
      (node (ref "R5") (pin "2") (pinfunction "2_2") (pintype "passive"))
    )
    (net (code "20") (name "/DR6") (class "Default")
      (node (ref "L10_6") (pin "C") (pinfunction "C_C") (pintype "passive"))
      (node (ref "L11_6") (pin "C") (pinfunction "C_C") (pintype "passive"))
      (node (ref "L12_6") (pin "C") (pinfunction "C_C") (pintype "passive"))
      (node (ref "L1_6") (pin "C") (pinfunction "C_C") (pintype "passive"))
      (node (ref "L2_6") (pin "C") (pinfunction "C_C") (pintype "passive"))
      (node (ref "L3_6") (pin "C") (pinfunction "C_C") (pintype "passive"))
      (node (ref "L4_6") (pin "C") (pinfunction "C_C") (pintype "passive"))
      (node (ref "L5_6") (pin "C") (pinfunction "C_C") (pintype "passive"))
      (node (ref "L6_1") (pin "A") (pinfunction "A_A") (pintype "passive"))
      (node (ref "L6_10") (pin "A") (pinfunction "A_A") (pintype "passive"))
      (node (ref "L6_11") (pin "A") (pinfunction "A_A") (pintype "passive"))
      (node (ref "L6_12") (pin "A") (pinfunction "A_A") (pintype "passive"))
      (node (ref "L6_2") (pin "A") (pinfunction "A_A") (pintype "passive"))
      (node (ref "L6_3") (pin "A") (pinfunction "A_A") (pintype "passive"))
      (node (ref "L6_4") (pin "A") (pinfunction "A_A") (pintype "passive"))
      (node (ref "L6_5") (pin "A") (pinfunction "A_A") (pintype "passive"))
      (node (ref "L6_7") (pin "A") (pinfunction "A_A") (pintype "passive"))
      (node (ref "L6_8") (pin "A") (pinfunction "A_A") (pintype "passive"))
      (node (ref "L6_9") (pin "A") (pinfunction "A_A") (pintype "passive"))
      (node (ref "L7_6") (pin "C") (pinfunction "C_C") (pintype "passive"))
      (node (ref "L8_6") (pin "C") (pinfunction "C_C") (pintype "passive"))
      (node (ref "L9_6") (pin "C") (pinfunction "C_C") (pintype "passive"))
      (node (ref "R6") (pin "2") (pinfunction "2_2") (pintype "passive"))
    )
    (net (code "21") (name "/DR7") (class "Default")
      (node (ref "L10_7") (pin "C") (pinfunction "C_C") (pintype "passive"))
      (node (ref "L11_7") (pin "C") (pinfunction "C_C") (pintype "passive"))
      (node (ref "L12_7") (pin "C") (pinfunction "C_C") (pintype "passive"))
      (node (ref "L1_7") (pin "C") (pinfunction "C_C") (pintype "passive"))
      (node (ref "L2_7") (pin "C") (pinfunction "C_C") (pintype "passive"))
      (node (ref "L3_7") (pin "C") (pinfunction "C_C") (pintype "passive"))
      (node (ref "L4_7") (pin "C") (pinfunction "C_C") (pintype "passive"))
      (node (ref "L5_7") (pin "C") (pinfunction "C_C") (pintype "passive"))
      (node (ref "L6_7") (pin "C") (pinfunction "C_C") (pintype "passive"))
      (node (ref "L7_1") (pin "A") (pinfunction "A_A") (pintype "passive"))
      (node (ref "L7_10") (pin "A") (pinfunction "A_A") (pintype "passive"))
      (node (ref "L7_11") (pin "A") (pinfunction "A_A") (pintype "passive"))
      (node (ref "L7_12") (pin "A") (pinfunction "A_A") (pintype "passive"))
      (node (ref "L7_2") (pin "A") (pinfunction "A_A") (pintype "passive"))
      (node (ref "L7_3") (pin "A") (pinfunction "A_A") (pintype "passive"))
      (node (ref "L7_4") (pin "A") (pinfunction "A_A") (pintype "passive"))
      (node (ref "L7_5") (pin "A") (pinfunction "A_A") (pintype "passive"))
      (node (ref "L7_6") (pin "A") (pinfunction "A_A") (pintype "passive"))
      (node (ref "L7_8") (pin "A") (pinfunction "A_A") (pintype "passive"))
      (node (ref "L7_9") (pin "A") (pinfunction "A_A") (pintype "passive"))
      (node (ref "L8_7") (pin "C") (pinfunction "C_C") (pintype "passive"))
      (node (ref "L9_7") (pin "C") (pinfunction "C_C") (pintype "passive"))
      (node (ref "R7") (pin "2") (pinfunction "2_2") (pintype "passive"))
    )
    (net (code "22") (name "/DR8") (class "Default")
      (node (ref "L10_8") (pin "C") (pinfunction "C_C") (pintype "passive"))
      (node (ref "L11_8") (pin "C") (pinfunction "C_C") (pintype "passive"))
      (node (ref "L12_8") (pin "C") (pinfunction "C_C") (pintype "passive"))
      (node (ref "L1_8") (pin "C") (pinfunction "C_C") (pintype "passive"))
      (node (ref "L2_8") (pin "C") (pinfunction "C_C") (pintype "passive"))
      (node (ref "L3_8") (pin "C") (pinfunction "C_C") (pintype "passive"))
      (node (ref "L4_8") (pin "C") (pinfunction "C_C") (pintype "passive"))
      (node (ref "L5_8") (pin "C") (pinfunction "C_C") (pintype "passive"))
      (node (ref "L6_8") (pin "C") (pinfunction "C_C") (pintype "passive"))
      (node (ref "L7_8") (pin "C") (pinfunction "C_C") (pintype "passive"))
      (node (ref "L8_1") (pin "A") (pinfunction "A_A") (pintype "passive"))
      (node (ref "L8_10") (pin "A") (pinfunction "A_A") (pintype "passive"))
      (node (ref "L8_11") (pin "A") (pinfunction "A_A") (pintype "passive"))
      (node (ref "L8_12") (pin "A") (pinfunction "A_A") (pintype "passive"))
      (node (ref "L8_2") (pin "A") (pinfunction "A_A") (pintype "passive"))
      (node (ref "L8_3") (pin "A") (pinfunction "A_A") (pintype "passive"))
      (node (ref "L8_4") (pin "A") (pinfunction "A_A") (pintype "passive"))
      (node (ref "L8_5") (pin "A") (pinfunction "A_A") (pintype "passive"))
      (node (ref "L8_6") (pin "A") (pinfunction "A_A") (pintype "passive"))
      (node (ref "L8_7") (pin "A") (pinfunction "A_A") (pintype "passive"))
      (node (ref "L8_9") (pin "A") (pinfunction "A_A") (pintype "passive"))
      (node (ref "L9_8") (pin "C") (pinfunction "C_C") (pintype "passive"))
      (node (ref "R8") (pin "2") (pinfunction "2_2") (pintype "passive"))
    )
    (net (code "23") (name "/DR9") (class "Default")
      (node (ref "L10_9") (pin "C") (pinfunction "C_C") (pintype "passive"))
      (node (ref "L11_9") (pin "C") (pinfunction "C_C") (pintype "passive"))
      (node (ref "L12_9") (pin "C") (pinfunction "C_C") (pintype "passive"))
      (node (ref "L1_9") (pin "C") (pinfunction "C_C") (pintype "passive"))
      (node (ref "L2_9") (pin "C") (pinfunction "C_C") (pintype "passive"))
      (node (ref "L3_9") (pin "C") (pinfunction "C_C") (pintype "passive"))
      (node (ref "L4_9") (pin "C") (pinfunction "C_C") (pintype "passive"))
      (node (ref "L5_9") (pin "C") (pinfunction "C_C") (pintype "passive"))
      (node (ref "L6_9") (pin "C") (pinfunction "C_C") (pintype "passive"))
      (node (ref "L7_9") (pin "C") (pinfunction "C_C") (pintype "passive"))
      (node (ref "L8_9") (pin "C") (pinfunction "C_C") (pintype "passive"))
      (node (ref "L9_1") (pin "A") (pinfunction "A_A") (pintype "passive"))
      (node (ref "L9_10") (pin "A") (pinfunction "A_A") (pintype "passive"))
      (node (ref "L9_11") (pin "A") (pinfunction "A_A") (pintype "passive"))
      (node (ref "L9_12") (pin "A") (pinfunction "A_A") (pintype "passive"))
      (node (ref "L9_2") (pin "A") (pinfunction "A_A") (pintype "passive"))
      (node (ref "L9_3") (pin "A") (pinfunction "A_A") (pintype "passive"))
      (node (ref "L9_4") (pin "A") (pinfunction "A_A") (pintype "passive"))
      (node (ref "L9_5") (pin "A") (pinfunction "A_A") (pintype "passive"))
      (node (ref "L9_6") (pin "A") (pinfunction "A_A") (pintype "passive"))
      (node (ref "L9_7") (pin "A") (pinfunction "A_A") (pintype "passive"))
      (node (ref "L9_8") (pin "A") (pinfunction "A_A") (pintype "passive"))
      (node (ref "R9") (pin "2") (pinfunction "2_2") (pintype "passive"))
    )
    (net (code "24") (name "/DR10") (class "Default")
      (node (ref "L10_1") (pin "A") (pinfunction "A_A") (pintype "passive"))
      (node (ref "L10_11") (pin "A") (pinfunction "A_A") (pintype "passive"))
      (node (ref "L10_12") (pin "A") (pinfunction "A_A") (pintype "passive"))
      (node (ref "L10_2") (pin "A") (pinfunction "A_A") (pintype "passive"))
      (node (ref "L10_3") (pin "A") (pinfunction "A_A") (pintype "passive"))
      (node (ref "L10_4") (pin "A") (pinfunction "A_A") (pintype "passive"))
      (node (ref "L10_5") (pin "A") (pinfunction "A_A") (pintype "passive"))
      (node (ref "L10_6") (pin "A") (pinfunction "A_A") (pintype "passive"))
      (node (ref "L10_7") (pin "A") (pinfunction "A_A") (pintype "passive"))
      (node (ref "L10_8") (pin "A") (pinfunction "A_A") (pintype "passive"))
      (node (ref "L10_9") (pin "A") (pinfunction "A_A") (pintype "passive"))
      (node (ref "L11_10") (pin "C") (pinfunction "C_C") (pintype "passive"))
      (node (ref "L12_10") (pin "C") (pinfunction "C_C") (pintype "passive"))
      (node (ref "L1_10") (pin "C") (pinfunction "C_C") (pintype "passive"))
      (node (ref "L2_10") (pin "C") (pinfunction "C_C") (pintype "passive"))
      (node (ref "L3_10") (pin "C") (pinfunction "C_C") (pintype "passive"))
      (node (ref "L4_10") (pin "C") (pinfunction "C_C") (pintype "passive"))
      (node (ref "L5_10") (pin "C") (pinfunction "C_C") (pintype "passive"))
      (node (ref "L6_10") (pin "C") (pinfunction "C_C") (pintype "passive"))
      (node (ref "L7_10") (pin "C") (pinfunction "C_C") (pintype "passive"))
      (node (ref "L8_10") (pin "C") (pinfunction "C_C") (pintype "passive"))
      (node (ref "L9_10") (pin "C") (pinfunction "C_C") (pintype "passive"))
      (node (ref "R10") (pin "2") (pinfunction "2_2") (pintype "passive"))
    )
    (net (code "25") (name "/DR11") (class "Default")
      (node (ref "L10_11") (pin "C") (pinfunction "C_C") (pintype "passive"))
      (node (ref "L11_1") (pin "A") (pinfunction "A_A") (pintype "passive"))
      (node (ref "L11_10") (pin "A") (pinfunction "A_A") (pintype "passive"))
      (node (ref "L11_12") (pin "A") (pinfunction "A_A") (pintype "passive"))
      (node (ref "L11_2") (pin "A") (pinfunction "A_A") (pintype "passive"))
      (node (ref "L11_3") (pin "A") (pinfunction "A_A") (pintype "passive"))
      (node (ref "L11_4") (pin "A") (pinfunction "A_A") (pintype "passive"))
      (node (ref "L11_5") (pin "A") (pinfunction "A_A") (pintype "passive"))
      (node (ref "L11_6") (pin "A") (pinfunction "A_A") (pintype "passive"))
      (node (ref "L11_7") (pin "A") (pinfunction "A_A") (pintype "passive"))
      (node (ref "L11_8") (pin "A") (pinfunction "A_A") (pintype "passive"))
      (node (ref "L11_9") (pin "A") (pinfunction "A_A") (pintype "passive"))
      (node (ref "L12_11") (pin "C") (pinfunction "C_C") (pintype "passive"))
      (node (ref "L1_11") (pin "C") (pinfunction "C_C") (pintype "passive"))
      (node (ref "L2_11") (pin "C") (pinfunction "C_C") (pintype "passive"))
      (node (ref "L3_11") (pin "C") (pinfunction "C_C") (pintype "passive"))
      (node (ref "L4_11") (pin "C") (pinfunction "C_C") (pintype "passive"))
      (node (ref "L5_11") (pin "C") (pinfunction "C_C") (pintype "passive"))
      (node (ref "L6_11") (pin "C") (pinfunction "C_C") (pintype "passive"))
      (node (ref "L7_11") (pin "C") (pinfunction "C_C") (pintype "passive"))
      (node (ref "L8_11") (pin "C") (pinfunction "C_C") (pintype "passive"))
      (node (ref "L9_11") (pin "C") (pinfunction "C_C") (pintype "passive"))
      (node (ref "R11") (pin "2") (pinfunction "2_2") (pintype "passive"))
    )
    (net (code "26") (name "/DR12") (class "Default")
      (node (ref "L10_12") (pin "C") (pinfunction "C_C") (pintype "passive"))
      (node (ref "L11_12") (pin "C") (pinfunction "C_C") (pintype "passive"))
      (node (ref "L12_1") (pin "A") (pinfunction "A_A") (pintype "passive"))
      (node (ref "L12_10") (pin "A") (pinfunction "A_A") (pintype "passive"))
      (node (ref "L12_11") (pin "A") (pinfunction "A_A") (pintype "passive"))
      (node (ref "L12_2") (pin "A") (pinfunction "A_A") (pintype "passive"))
      (node (ref "L12_3") (pin "A") (pinfunction "A_A") (pintype "passive"))
      (node (ref "L12_4") (pin "A") (pinfunction "A_A") (pintype "passive"))
      (node (ref "L12_5") (pin "A") (pinfunction "A_A") (pintype "passive"))
      (node (ref "L12_6") (pin "A") (pinfunction "A_A") (pintype "passive"))
      (node (ref "L12_7") (pin "A") (pinfunction "A_A") (pintype "passive"))
      (node (ref "L12_8") (pin "A") (pinfunction "A_A") (pintype "passive"))
      (node (ref "L12_9") (pin "A") (pinfunction "A_A") (pintype "passive"))
      (node (ref "L1_12") (pin "C") (pinfunction "C_C") (pintype "passive"))
      (node (ref "L2_12") (pin "C") (pinfunction "C_C") (pintype "passive"))
      (node (ref "L3_12") (pin "C") (pinfunction "C_C") (pintype "passive"))
      (node (ref "L4_12") (pin "C") (pinfunction "C_C") (pintype "passive"))
      (node (ref "L5_12") (pin "C") (pinfunction "C_C") (pintype "passive"))
      (node (ref "L6_12") (pin "C") (pinfunction "C_C") (pintype "passive"))
      (node (ref "L7_12") (pin "C") (pinfunction "C_C") (pintype "passive"))
      (node (ref "L8_12") (pin "C") (pinfunction "C_C") (pintype "passive"))
      (node (ref "L9_12") (pin "C") (pinfunction "C_C") (pintype "passive"))
      (node (ref "R12") (pin "2") (pinfunction "2_2") (pintype "passive"))
    )
    (net (code "27") (name "/MISO") (class "Default")
      (node (ref "IC1") (pin "16") (pinfunction "PB4(MISO)_16") (pintype "bidirectional"))
      (node (ref "J1") (pin "P$1") (pinfunction "1_P$1") (pintype "passive"))
    )
    (net (code "28") (name "/MOSI") (class "Default")
      (node (ref "IC1") (pin "15") (pinfunction "PB3(MOSI/OC2)_15") (pintype "bidirectional"))
      (node (ref "J1") (pin "P$4") (pinfunction "4_P$4") (pintype "passive"))
    )
    (net (code "29") (name "/RESET") (class "Default")
      (node (ref "IC1") (pin "29") (pinfunction "PC6(/RESET)_29") (pintype "bidirectional"))
      (node (ref "J1") (pin "P$5") (pinfunction "5_P$5") (pintype "passive"))
    )
    (net (code "30") (name "/SCK") (class "Default")
      (node (ref "IC1") (pin "17") (pinfunction "PB5(SCK)_17") (pintype "bidirectional"))
      (node (ref "J1") (pin "P$3") (pinfunction "3_P$3") (pintype "passive"))
    )
    (net (code "31") (name "GNDA") (class "Default")
      (node (ref "C1") (pin "2") (pinfunction "2_2") (pintype "passive"))
      (node (ref "C2") (pin "2") (pinfunction "2_2") (pintype "passive"))
      (node (ref "DOWNSW") (pin "B2") (pinfunction "2_B2") (pintype "passive"))
      (node (ref "IC1") (pin "21") (pinfunction "GND_21") (pintype "power_in"))
      (node (ref "IC1") (pin "3") (pinfunction "GND_3") (pintype "power_in"))
      (node (ref "IC1") (pin "5") (pinfunction "GND_5") (pintype "power_in"))
      (node (ref "J1") (pin "P$7") (pinfunction "6_P$7") (pintype "passive"))
      (node (ref "TP1") (pin "TP") (pinfunction "TP_TP") (pintype "input"))
      (node (ref "UPSW") (pin "B2") (pinfunction "2_B2") (pintype "passive"))
    )
    (net (code "32") (name "Net-(DOWNSW-1)") (class "Default")
      (node (ref "DOWNSW") (pin "A2") (pinfunction "1_A2") (pintype "passive"))
      (node (ref "IC1") (pin "13") (pinfunction "PB1(OC1A)_13") (pintype "bidirectional"))
    )
    (net (code "33") (name "Net-(IC1-PB2(SS{slash}OC1B))") (class "Default")
      (node (ref "IC1") (pin "14") (pinfunction "PB2(SS/OC1B)_14") (pintype "bidirectional"))
      (node (ref "UPSW") (pin "A2") (pinfunction "1_A2") (pintype "passive"))
    )
    (net (code "34") (name "Net-(IC1-PB6(XTAL1{slash}TOSC1))") (class "Default")
      (node (ref "C1") (pin "1") (pinfunction "1_1") (pintype "passive"))
      (node (ref "IC1") (pin "7") (pinfunction "PB6(XTAL1/TOSC1)_7") (pintype "bidirectional"))
      (node (ref "Q1") (pin "1") (pinfunction "1_1") (pintype "passive"))
    )
    (net (code "35") (name "Net-(IC1-PB7(XTAL2{slash}TOSC2))") (class "Default")
      (node (ref "C2") (pin "1") (pinfunction "1_1") (pintype "passive"))
      (node (ref "IC1") (pin "8") (pinfunction "PB7(XTAL2/TOSC2)_8") (pintype "bidirectional"))
      (node (ref "Q1") (pin "3") (pinfunction "3_3") (pintype "passive"))
    )
    (net (code "36") (name "unconnected-(IC1-ADC6-Pad19)") (class "Default")
      (node (ref "IC1") (pin "19") (pinfunction "ADC6_19") (pintype "bidirectional"))
    )
    (net (code "37") (name "unconnected-(IC1-ADC7-Pad22)") (class "Default")
      (node (ref "IC1") (pin "22") (pinfunction "ADC7_22") (pintype "bidirectional"))
    )
    (net (code "38") (name "unconnected-(IC1-AREF-Pad20)") (class "Default")
      (node (ref "IC1") (pin "20") (pinfunction "AREF_20") (pintype "passive"))
    )
    (net (code "39") (name "unconnected-(IC1-PB0(ICP)-Pad12)") (class "Default")
      (node (ref "IC1") (pin "12") (pinfunction "PB0(ICP)_12") (pintype "bidirectional"))
    )
    (net (code "40") (name "unconnected-(IC1-PC4(ADC4{slash}SDA)-Pad27)") (class "Default")
      (node (ref "IC1") (pin "27") (pinfunction "PC4(ADC4/SDA)_27") (pintype "bidirectional"))
    )
    (net (code "41") (name "unconnected-(IC1-PC5(ADC5{slash}SCL)-Pad28)") (class "Default")
      (node (ref "IC1") (pin "28") (pinfunction "PC5(ADC5/SCL)_28") (pintype "bidirectional"))
    )
    (net (code "42") (name "unconnected-(Q1-Pad2)") (class "Default")
      (node (ref "Q1") (pin "2") (pinfunction "2_2") (pintype "passive"))
    )
    (net (code "43") (name "unconnected-(Q1-Pad4)") (class "Default")
      (node (ref "Q1") (pin "4") (pinfunction "4_4") (pintype "passive"))
    )
  )
)
